# tactile_sensor.net
KiCad netlist of a schematic drawn in EAGLE
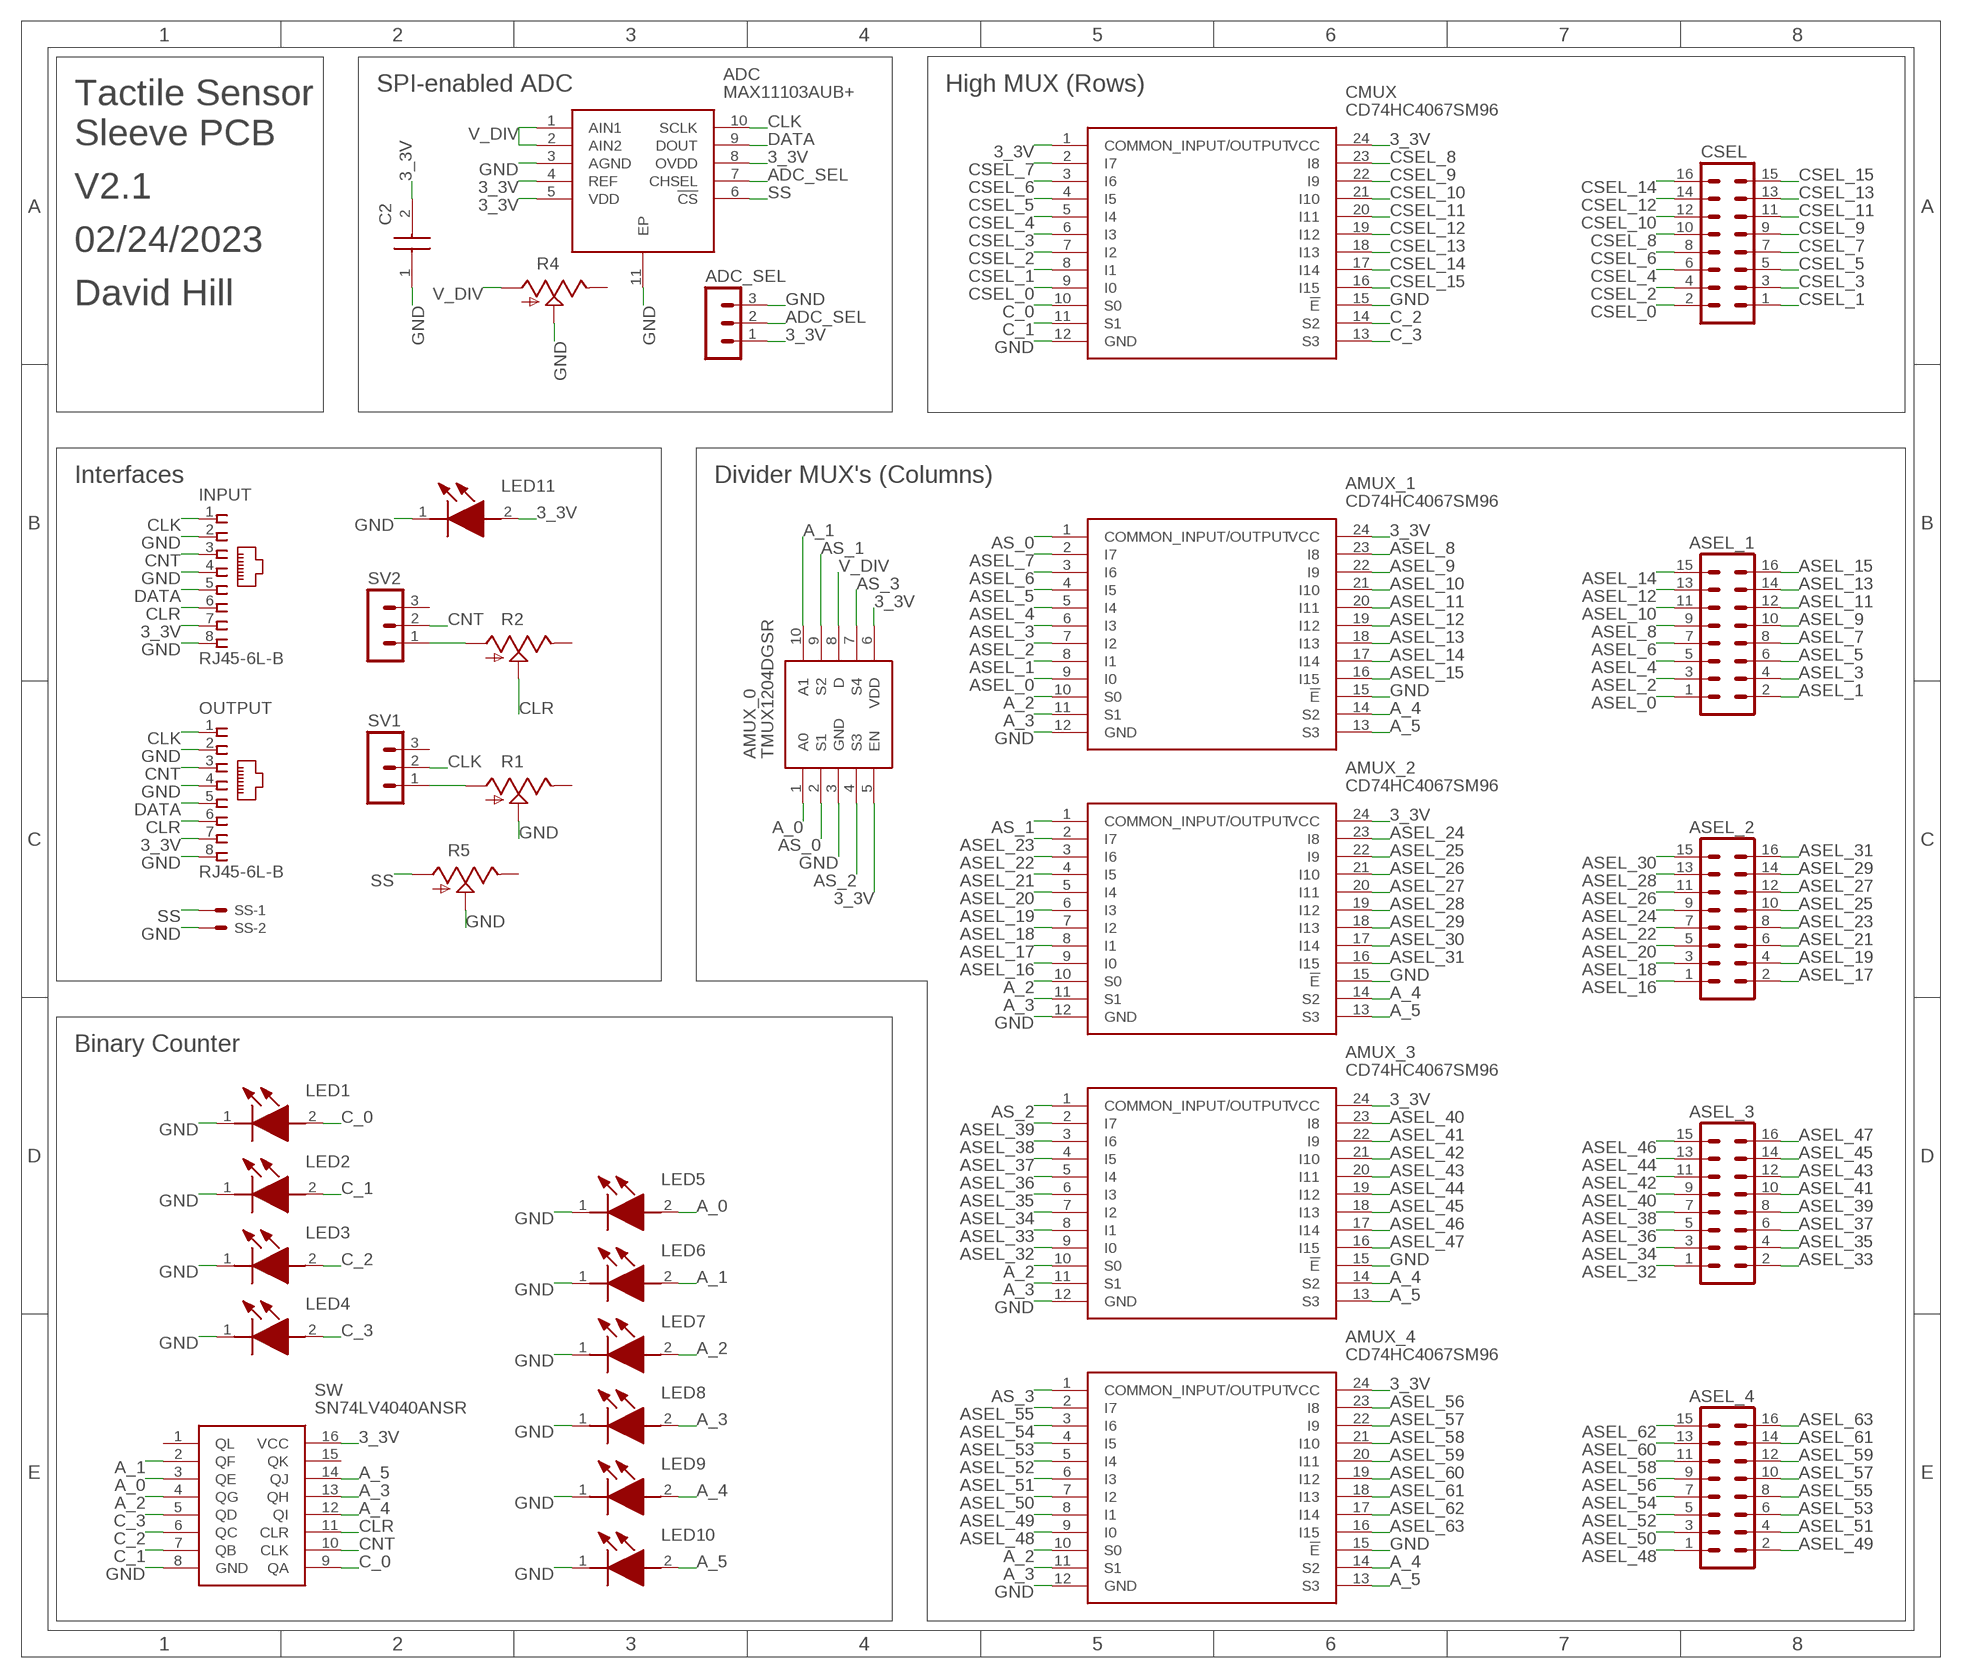
[diagram p0: schematic, sheet 1]

(export (version "E")
  (design (tool "Eeschema 10.0.6"))
  (components
    (comp (ref "ADC")
      (value "MAX11103AUB+")
      (footprint "eagle-import:SOP50P490X110-11N")
      (fields (field (name "MOUSER_PART_NUMBER") "700-MAX11103AUB+"))
      (libsource (lib "eagle-import") (part "MAX11103AUB+"))
    )
    (comp (ref "ADC_SEL")
      (value "MA03-1")
      (footprint "eagle-import:MA03-1")
      (libsource (lib "eagle-import") (part "MA03-1"))
    )
    (comp (ref "AMUX_0")
      (value "TMUX1204DGSR")
      (footprint "eagle-import:SOP50P490X110-10N")
      (fields (field (name "MOUSER_PART_NUMBER") "595-TMUX1204DGSR"))
      (libsource (lib "eagle-import") (part "TMUX1204DGSR"))
    )
    (comp (ref "AMUX_1")
      (value "CD74HC4067SM96")
      (footprint "eagle-import:SOP65P780X200-24N")
      (fields (field (name "MOUSER_PART_NUMBER") "595-CD74HC4067SM96"))
      (libsource (lib "eagle-import") (part "CD74HC4067SM96"))
    )
    (comp (ref "AMUX_2")
      (value "CD74HC4067SM96")
      (footprint "eagle-import:SOP65P780X200-24N")
      (fields (field (name "MOUSER_PART_NUMBER") "595-CD74HC4067SM96"))
      (libsource (lib "eagle-import") (part "CD74HC4067SM96"))
    )
    (comp (ref "AMUX_3")
      (value "CD74HC4067SM96")
      (footprint "eagle-import:SOP65P780X200-24N")
      (fields (field (name "MOUSER_PART_NUMBER") "595-CD74HC4067SM96"))
      (libsource (lib "eagle-import") (part "CD74HC4067SM96"))
    )
    (comp (ref "AMUX_4")
      (value "CD74HC4067SM96")
      (footprint "eagle-import:SOP65P780X200-24N")
      (fields (field (name "MOUSER_PART_NUMBER") "595-CD74HC4067SM96"))
      (libsource (lib "eagle-import") (part "CD74HC4067SM96"))
    )
    (comp (ref "ASEL_1")
      (value "MA08-2")
      (footprint "eagle-import:MA08-2")
      (libsource (lib "eagle-import") (part "MA08-2"))
    )
    (comp (ref "ASEL_2")
      (value "MA08-2")
      (footprint "eagle-import:MA08-2")
      (libsource (lib "eagle-import") (part "MA08-2"))
    )
    (comp (ref "ASEL_3")
      (value "MA08-2")
      (footprint "eagle-import:MA08-2")
      (libsource (lib "eagle-import") (part "MA08-2"))
    )
    (comp (ref "ASEL_4")
      (value "MA08-2")
      (footprint "eagle-import:MA08-2")
      (libsource (lib "eagle-import") (part "MA08-2"))
    )
    (comp (ref "C2")
      (value "C2012X7S1E106K125AE")
      (footprint "eagle-import:C2012_COMMERCIAL")
      (fields (field (name "MOUSER_PART_NUMBER") "810-C2012X7S1E106125"))
      (libsource (lib "eagle-import") (part "C2012X7S1E106K125AE"))
    )
    (comp (ref "CMUX")
      (value "CD74HC4067SM96")
      (footprint "eagle-import:SOP65P780X200-24N")
      (fields (field (name "MOUSER_PART_NUMBER") "595-CD74HC4067SM96"))
      (libsource (lib "eagle-import") (part "CD74HC4067SM96"))
    )
    (comp (ref "CSEL")
      (value "MA08-2")
      (footprint "eagle-import:MA08-2")
      (libsource (lib "eagle-import") (part "MA08-2"))
    )
    (comp (ref "INPUT")
      (value "RJ45-6L-B")
      (footprint "eagle-import:RJ45-NO-SHIELD")
      (libsource (lib "eagle-import") (part "RJ45-6L-B"))
    )
    (comp (ref "LED1")
      (value "APHCM2012QBC_D-F01")
      (footprint "eagle-import:APHCM2012QBCDF01")
      (fields
        (field (name "MANUFACTURER_PART_NUMBER") "APHCM2012QBC/D-F01")
        (field (name "MOUSER_PART_NUMBER") "604-APHCM2012QBC/D")
      )
      (libsource (lib "eagle-import") (part "APHCM2012QBC_D-F01"))
    )
    (comp (ref "LED2")
      (value "APHCM2012QBC_D-F01")
      (footprint "eagle-import:APHCM2012QBCDF01")
      (fields
        (field (name "MANUFACTURER_PART_NUMBER") "APHCM2012QBC/D-F01")
        (field (name "MOUSER_PART_NUMBER") "604-APHCM2012QBC/D")
      )
      (libsource (lib "eagle-import") (part "APHCM2012QBC_D-F01"))
    )
    (comp (ref "LED3")
      (value "APHCM2012QBC_D-F01")
      (footprint "eagle-import:APHCM2012QBCDF01")
      (fields
        (field (name "MANUFACTURER_PART_NUMBER") "APHCM2012QBC/D-F01")
        (field (name "MOUSER_PART_NUMBER") "604-APHCM2012QBC/D")
      )
      (libsource (lib "eagle-import") (part "APHCM2012QBC_D-F01"))
    )
    (comp (ref "LED4")
      (value "APHCM2012QBC_D-F01")
      (footprint "eagle-import:APHCM2012QBCDF01")
      (fields
        (field (name "MANUFACTURER_PART_NUMBER") "APHCM2012QBC/D-F01")
        (field (name "MOUSER_PART_NUMBER") "604-APHCM2012QBC/D")
      )
      (libsource (lib "eagle-import") (part "APHCM2012QBC_D-F01"))
    )
    (comp (ref "LED5")
      (value "APHCM2012QBC_D-F01")
      (footprint "eagle-import:APHCM2012QBCDF01")
      (fields
        (field (name "MANUFACTURER_PART_NUMBER") "APHCM2012QBC/D-F01")
        (field (name "MOUSER_PART_NUMBER") "604-APHCM2012QBC/D")
      )
      (libsource (lib "eagle-import") (part "APHCM2012QBC_D-F01"))
    )
    (comp (ref "LED6")
      (value "APHCM2012QBC_D-F01")
      (footprint "eagle-import:APHCM2012QBCDF01")
      (fields
        (field (name "MANUFACTURER_PART_NUMBER") "APHCM2012QBC/D-F01")
        (field (name "MOUSER_PART_NUMBER") "604-APHCM2012QBC/D")
      )
      (libsource (lib "eagle-import") (part "APHCM2012QBC_D-F01"))
    )
    (comp (ref "LED7")
      (value "APHCM2012QBC_D-F01")
      (footprint "eagle-import:APHCM2012QBCDF01")
      (fields
        (field (name "MANUFACTURER_PART_NUMBER") "APHCM2012QBC/D-F01")
        (field (name "MOUSER_PART_NUMBER") "604-APHCM2012QBC/D")
      )
      (libsource (lib "eagle-import") (part "APHCM2012QBC_D-F01"))
    )
    (comp (ref "LED8")
      (value "APHCM2012QBC_D-F01")
      (footprint "eagle-import:APHCM2012QBCDF01")
      (fields
        (field (name "MANUFACTURER_PART_NUMBER") "APHCM2012QBC/D-F01")
        (field (name "MOUSER_PART_NUMBER") "604-APHCM2012QBC/D")
      )
      (libsource (lib "eagle-import") (part "APHCM2012QBC_D-F01"))
    )
    (comp (ref "LED9")
      (value "APHCM2012QBC_D-F01")
      (footprint "eagle-import:APHCM2012QBCDF01")
      (fields
        (field (name "MANUFACTURER_PART_NUMBER") "APHCM2012QBC/D-F01")
        (field (name "MOUSER_PART_NUMBER") "604-APHCM2012QBC/D")
      )
      (libsource (lib "eagle-import") (part "APHCM2012QBC_D-F01"))
    )
    (comp (ref "LED10")
      (value "APHCM2012QBC_D-F01")
      (footprint "eagle-import:APHCM2012QBCDF01")
      (fields
        (field (name "MANUFACTURER_PART_NUMBER") "APHCM2012QBC/D-F01")
        (field (name "MOUSER_PART_NUMBER") "604-APHCM2012QBC/D")
      )
      (libsource (lib "eagle-import") (part "APHCM2012QBC_D-F01"))
    )
    (comp (ref "LED11")
      (value "APHCM2012QBC_D-F01")
      (footprint "eagle-import:APHCM2012QBCDF01")
      (fields
        (field (name "MANUFACTURER_PART_NUMBER") "APHCM2012QBC/D-F01")
        (field (name "MOUSER_PART_NUMBER") "604-APHCM2012QBC/D")
      )
      (libsource (lib "eagle-import") (part "APHCM2012QBC_D-F01"))
    )
    (comp (ref "OUTPUT")
      (value "RJ45-6L-B")
      (footprint "eagle-import:RJ45-NO-SHIELD")
      (libsource (lib "eagle-import") (part "RJ45-6L-B"))
    )
    (comp (ref "R1")
      (value "TRIM_US-B25P")
      (footprint "eagle-import:B25P")
      (libsource (lib "eagle-import") (part "TRIM_US-B25P"))
    )
    (comp (ref "R2")
      (value "TRIM_US-B25P")
      (footprint "eagle-import:B25P")
      (libsource (lib "eagle-import") (part "TRIM_US-B25P"))
    )
    (comp (ref "R4")
      (value "TRIM_US-B25P")
      (footprint "eagle-import:B25P")
      (libsource (lib "eagle-import") (part "TRIM_US-B25P"))
    )
    (comp (ref "R5")
      (value "TRIM_US-B25P")
      (footprint "eagle-import:B25P")
      (libsource (lib "eagle-import") (part "TRIM_US-B25P"))
    )
    (comp (ref "SS")
      (value "22-23-2021")
      (footprint "eagle-import:22-23-2021")
      (fields (field (name "MF") "MOLEX"))
      (libsource (lib "eagle-import") (part "22-23-2021"))
    )
    (comp (ref "SV1")
      (value "MA03-1")
      (footprint "eagle-import:MA03-1")
      (libsource (lib "eagle-import") (part "MA03-1"))
    )
    (comp (ref "SV2")
      (value "MA03-1")
      (footprint "eagle-import:MA03-1")
      (libsource (lib "eagle-import") (part "MA03-1"))
    )
    (comp (ref "SW")
      (value "SN74LV4040ANSR")
      (footprint "eagle-import:SOIC127P780X200-16N")
      (fields (field (name "MOUSER_PART_NUMBER") "595-SN74LV4040ANSR"))
      (libsource (lib "eagle-import") (part "SN74LV4040ANSR"))
    )
  )
  (nets
    (net (code "1") (name "/3_3V") (class "Default")
      (node (ref "ADC") (pin "4") (pinfunction "REF_4") (pintype "input"))
      (node (ref "ADC") (pin "5") (pinfunction "VDD_5") (pintype "power_in"))
      (node (ref "ADC") (pin "8") (pinfunction "OVDD_8") (pintype "power_in"))
      (node (ref "ADC_SEL") (pin "1") (pinfunction "1_1") (pintype "passive"))
      (node (ref "AMUX_0") (pin "5") (pinfunction "EN_5") (pintype "input"))
      (node (ref "AMUX_0") (pin "6") (pinfunction "VDD_6") (pintype "power_in"))
      (node (ref "AMUX_1") (pin "24") (pinfunction "VCC_24") (pintype "bidirectional"))
      (node (ref "AMUX_2") (pin "24") (pinfunction "VCC_24") (pintype "bidirectional"))
      (node (ref "AMUX_3") (pin "24") (pinfunction "VCC_24") (pintype "bidirectional"))
      (node (ref "AMUX_4") (pin "24") (pinfunction "VCC_24") (pintype "bidirectional"))
      (node (ref "C2") (pin "2") (pinfunction "2_2") (pintype "bidirectional"))
      (node (ref "CMUX") (pin "1") (pinfunction "COMMON_INPUT/OUTPUT_1") (pintype "bidirectional"))
      (node (ref "CMUX") (pin "24") (pinfunction "VCC_24") (pintype "bidirectional"))
      (node (ref "INPUT") (pin "7") (pinfunction "7_7") (pintype "passive"))
      (node (ref "LED11") (pin "2") (pinfunction "A_2") (pintype "bidirectional"))
      (node (ref "OUTPUT") (pin "7") (pinfunction "7_7") (pintype "passive"))
      (node (ref "SW") (pin "16") (pinfunction "VCC_16") (pintype "bidirectional"))
    )
    (net (code "2") (name "/ADC_SEL") (class "Default")
      (node (ref "ADC") (pin "7") (pinfunction "CHSEL_7") (pintype "bidirectional"))
      (node (ref "ADC_SEL") (pin "2") (pinfunction "2_2") (pintype "passive"))
    )
    (net (code "3") (name "/ASEL_0") (class "Default")
      (node (ref "AMUX_1") (pin "9") (pinfunction "I0_9") (pintype "bidirectional"))
      (node (ref "ASEL_1") (pin "1") (pinfunction "1_1") (pintype "passive"))
    )
    (net (code "4") (name "/ASEL_1") (class "Default")
      (node (ref "AMUX_1") (pin "8") (pinfunction "I1_8") (pintype "bidirectional"))
      (node (ref "ASEL_1") (pin "2") (pinfunction "2_2") (pintype "passive"))
    )
    (net (code "5") (name "/ASEL_2") (class "Default")
      (node (ref "AMUX_1") (pin "7") (pinfunction "I2_7") (pintype "bidirectional"))
      (node (ref "ASEL_1") (pin "3") (pinfunction "3_3") (pintype "passive"))
    )
    (net (code "6") (name "/ASEL_3") (class "Default")
      (node (ref "AMUX_1") (pin "6") (pinfunction "I3_6") (pintype "bidirectional"))
      (node (ref "ASEL_1") (pin "4") (pinfunction "4_4") (pintype "passive"))
    )
    (net (code "7") (name "/ASEL_4") (class "Default")
      (node (ref "AMUX_1") (pin "5") (pinfunction "I4_5") (pintype "bidirectional"))
      (node (ref "ASEL_1") (pin "5") (pinfunction "5_5") (pintype "passive"))
    )
    (net (code "8") (name "/ASEL_5") (class "Default")
      (node (ref "AMUX_1") (pin "4") (pinfunction "I5_4") (pintype "bidirectional"))
      (node (ref "ASEL_1") (pin "6") (pinfunction "6_6") (pintype "passive"))
    )
    (net (code "9") (name "/ASEL_6") (class "Default")
      (node (ref "AMUX_1") (pin "3") (pinfunction "I6_3") (pintype "bidirectional"))
      (node (ref "ASEL_1") (pin "7") (pinfunction "7_7") (pintype "passive"))
    )
    (net (code "10") (name "/ASEL_7") (class "Default")
      (node (ref "AMUX_1") (pin "2") (pinfunction "I7_2") (pintype "bidirectional"))
      (node (ref "ASEL_1") (pin "8") (pinfunction "8_8") (pintype "passive"))
    )
    (net (code "11") (name "/ASEL_8") (class "Default")
      (node (ref "AMUX_1") (pin "23") (pinfunction "I8_23") (pintype "bidirectional"))
      (node (ref "ASEL_1") (pin "9") (pinfunction "9_9") (pintype "passive"))
    )
    (net (code "12") (name "/ASEL_9") (class "Default")
      (node (ref "AMUX_1") (pin "22") (pinfunction "I9_22") (pintype "bidirectional"))
      (node (ref "ASEL_1") (pin "10") (pinfunction "10_10") (pintype "passive"))
    )
    (net (code "13") (name "/ASEL_10") (class "Default")
      (node (ref "AMUX_1") (pin "21") (pinfunction "I10_21") (pintype "bidirectional"))
      (node (ref "ASEL_1") (pin "11") (pinfunction "11_11") (pintype "passive"))
    )
    (net (code "14") (name "/ASEL_11") (class "Default")
      (node (ref "AMUX_1") (pin "20") (pinfunction "I11_20") (pintype "bidirectional"))
      (node (ref "ASEL_1") (pin "12") (pinfunction "12_12") (pintype "passive"))
    )
    (net (code "15") (name "/ASEL_12") (class "Default")
      (node (ref "AMUX_1") (pin "19") (pinfunction "I12_19") (pintype "bidirectional"))
      (node (ref "ASEL_1") (pin "13") (pinfunction "13_13") (pintype "passive"))
    )
    (net (code "16") (name "/ASEL_13") (class "Default")
      (node (ref "AMUX_1") (pin "18") (pinfunction "I13_18") (pintype "bidirectional"))
      (node (ref "ASEL_1") (pin "14") (pinfunction "14_14") (pintype "passive"))
    )
    (net (code "17") (name "/ASEL_14") (class "Default")
      (node (ref "AMUX_1") (pin "17") (pinfunction "I14_17") (pintype "bidirectional"))
      (node (ref "ASEL_1") (pin "15") (pinfunction "15_15") (pintype "passive"))
    )
    (net (code "18") (name "/ASEL_15") (class "Default")
      (node (ref "AMUX_1") (pin "16") (pinfunction "I15_16") (pintype "bidirectional"))
      (node (ref "ASEL_1") (pin "16") (pinfunction "16_16") (pintype "passive"))
    )
    (net (code "19") (name "/ASEL_16") (class "Default")
      (node (ref "AMUX_2") (pin "9") (pinfunction "I0_9") (pintype "bidirectional"))
      (node (ref "ASEL_2") (pin "1") (pinfunction "1_1") (pintype "passive"))
    )
    (net (code "20") (name "/ASEL_17") (class "Default")
      (node (ref "AMUX_2") (pin "8") (pinfunction "I1_8") (pintype "bidirectional"))
      (node (ref "ASEL_2") (pin "2") (pinfunction "2_2") (pintype "passive"))
    )
    (net (code "21") (name "/ASEL_18") (class "Default")
      (node (ref "AMUX_2") (pin "7") (pinfunction "I2_7") (pintype "bidirectional"))
      (node (ref "ASEL_2") (pin "3") (pinfunction "3_3") (pintype "passive"))
    )
    (net (code "22") (name "/ASEL_19") (class "Default")
      (node (ref "AMUX_2") (pin "6") (pinfunction "I3_6") (pintype "bidirectional"))
      (node (ref "ASEL_2") (pin "4") (pinfunction "4_4") (pintype "passive"))
    )
    (net (code "23") (name "/ASEL_20") (class "Default")
      (node (ref "AMUX_2") (pin "5") (pinfunction "I4_5") (pintype "bidirectional"))
      (node (ref "ASEL_2") (pin "5") (pinfunction "5_5") (pintype "passive"))
    )
    (net (code "24") (name "/ASEL_21") (class "Default")
      (node (ref "AMUX_2") (pin "4") (pinfunction "I5_4") (pintype "bidirectional"))
      (node (ref "ASEL_2") (pin "6") (pinfunction "6_6") (pintype "passive"))
    )
    (net (code "25") (name "/ASEL_22") (class "Default")
      (node (ref "AMUX_2") (pin "3") (pinfunction "I6_3") (pintype "bidirectional"))
      (node (ref "ASEL_2") (pin "7") (pinfunction "7_7") (pintype "passive"))
    )
    (net (code "26") (name "/ASEL_23") (class "Default")
      (node (ref "AMUX_2") (pin "2") (pinfunction "I7_2") (pintype "bidirectional"))
      (node (ref "ASEL_2") (pin "8") (pinfunction "8_8") (pintype "passive"))
    )
    (net (code "27") (name "/ASEL_24") (class "Default")
      (node (ref "AMUX_2") (pin "23") (pinfunction "I8_23") (pintype "bidirectional"))
      (node (ref "ASEL_2") (pin "9") (pinfunction "9_9") (pintype "passive"))
    )
    (net (code "28") (name "/ASEL_25") (class "Default")
      (node (ref "AMUX_2") (pin "22") (pinfunction "I9_22") (pintype "bidirectional"))
      (node (ref "ASEL_2") (pin "10") (pinfunction "10_10") (pintype "passive"))
    )
    (net (code "29") (name "/ASEL_26") (class "Default")
      (node (ref "AMUX_2") (pin "21") (pinfunction "I10_21") (pintype "bidirectional"))
      (node (ref "ASEL_2") (pin "11") (pinfunction "11_11") (pintype "passive"))
    )
    (net (code "30") (name "/ASEL_27") (class "Default")
      (node (ref "AMUX_2") (pin "20") (pinfunction "I11_20") (pintype "bidirectional"))
      (node (ref "ASEL_2") (pin "12") (pinfunction "12_12") (pintype "passive"))
    )
    (net (code "31") (name "/ASEL_28") (class "Default")
      (node (ref "AMUX_2") (pin "19") (pinfunction "I12_19") (pintype "bidirectional"))
      (node (ref "ASEL_2") (pin "13") (pinfunction "13_13") (pintype "passive"))
    )
    (net (code "32") (name "/ASEL_29") (class "Default")
      (node (ref "AMUX_2") (pin "18") (pinfunction "I13_18") (pintype "bidirectional"))
      (node (ref "ASEL_2") (pin "14") (pinfunction "14_14") (pintype "passive"))
    )
    (net (code "33") (name "/ASEL_30") (class "Default")
      (node (ref "AMUX_2") (pin "17") (pinfunction "I14_17") (pintype "bidirectional"))
      (node (ref "ASEL_2") (pin "15") (pinfunction "15_15") (pintype "passive"))
    )
    (net (code "34") (name "/ASEL_31") (class "Default")
      (node (ref "AMUX_2") (pin "16") (pinfunction "I15_16") (pintype "bidirectional"))
      (node (ref "ASEL_2") (pin "16") (pinfunction "16_16") (pintype "passive"))
    )
    (net (code "35") (name "/ASEL_32") (class "Default")
      (node (ref "AMUX_3") (pin "9") (pinfunction "I0_9") (pintype "bidirectional"))
      (node (ref "ASEL_3") (pin "1") (pinfunction "1_1") (pintype "passive"))
    )
    (net (code "36") (name "/ASEL_33") (class "Default")
      (node (ref "AMUX_3") (pin "8") (pinfunction "I1_8") (pintype "bidirectional"))
      (node (ref "ASEL_3") (pin "2") (pinfunction "2_2") (pintype "passive"))
    )
    (net (code "37") (name "/ASEL_34") (class "Default")
      (node (ref "AMUX_3") (pin "7") (pinfunction "I2_7") (pintype "bidirectional"))
      (node (ref "ASEL_3") (pin "3") (pinfunction "3_3") (pintype "passive"))
    )
    (net (code "38") (name "/ASEL_35") (class "Default")
      (node (ref "AMUX_3") (pin "6") (pinfunction "I3_6") (pintype "bidirectional"))
      (node (ref "ASEL_3") (pin "4") (pinfunction "4_4") (pintype "passive"))
    )
    (net (code "39") (name "/ASEL_36") (class "Default")
      (node (ref "AMUX_3") (pin "5") (pinfunction "I4_5") (pintype "bidirectional"))
      (node (ref "ASEL_3") (pin "5") (pinfunction "5_5") (pintype "passive"))
    )
    (net (code "40") (name "/ASEL_37") (class "Default")
      (node (ref "AMUX_3") (pin "4") (pinfunction "I5_4") (pintype "bidirectional"))
      (node (ref "ASEL_3") (pin "6") (pinfunction "6_6") (pintype "passive"))
    )
    (net (code "41") (name "/ASEL_38") (class "Default")
      (node (ref "AMUX_3") (pin "3") (pinfunction "I6_3") (pintype "bidirectional"))
      (node (ref "ASEL_3") (pin "7") (pinfunction "7_7") (pintype "passive"))
    )
    (net (code "42") (name "/ASEL_39") (class "Default")
      (node (ref "AMUX_3") (pin "2") (pinfunction "I7_2") (pintype "bidirectional"))
      (node (ref "ASEL_3") (pin "8") (pinfunction "8_8") (pintype "passive"))
    )
    (net (code "43") (name "/ASEL_40") (class "Default")
      (node (ref "AMUX_3") (pin "23") (pinfunction "I8_23") (pintype "bidirectional"))
      (node (ref "ASEL_3") (pin "9") (pinfunction "9_9") (pintype "passive"))
    )
    (net (code "44") (name "/ASEL_41") (class "Default")
      (node (ref "AMUX_3") (pin "22") (pinfunction "I9_22") (pintype "bidirectional"))
      (node (ref "ASEL_3") (pin "10") (pinfunction "10_10") (pintype "passive"))
    )
    (net (code "45") (name "/ASEL_42") (class "Default")
      (node (ref "AMUX_3") (pin "21") (pinfunction "I10_21") (pintype "bidirectional"))
      (node (ref "ASEL_3") (pin "11") (pinfunction "11_11") (pintype "passive"))
    )
    (net (code "46") (name "/ASEL_43") (class "Default")
      (node (ref "AMUX_3") (pin "20") (pinfunction "I11_20") (pintype "bidirectional"))
      (node (ref "ASEL_3") (pin "12") (pinfunction "12_12") (pintype "passive"))
    )
    (net (code "47") (name "/ASEL_44") (class "Default")
      (node (ref "AMUX_3") (pin "19") (pinfunction "I12_19") (pintype "bidirectional"))
      (node (ref "ASEL_3") (pin "13") (pinfunction "13_13") (pintype "passive"))
    )
    (net (code "48") (name "/ASEL_45") (class "Default")
      (node (ref "AMUX_3") (pin "18") (pinfunction "I13_18") (pintype "bidirectional"))
      (node (ref "ASEL_3") (pin "14") (pinfunction "14_14") (pintype "passive"))
    )
    (net (code "49") (name "/ASEL_46") (class "Default")
      (node (ref "AMUX_3") (pin "17") (pinfunction "I14_17") (pintype "bidirectional"))
      (node (ref "ASEL_3") (pin "15") (pinfunction "15_15") (pintype "passive"))
    )
    (net (code "50") (name "/ASEL_47") (class "Default")
      (node (ref "AMUX_3") (pin "16") (pinfunction "I15_16") (pintype "bidirectional"))
      (node (ref "ASEL_3") (pin "16") (pinfunction "16_16") (pintype "passive"))
    )
    (net (code "51") (name "/ASEL_48") (class "Default")
      (node (ref "AMUX_4") (pin "9") (pinfunction "I0_9") (pintype "bidirectional"))
      (node (ref "ASEL_4") (pin "1") (pinfunction "1_1") (pintype "passive"))
    )
    (net (code "52") (name "/ASEL_49") (class "Default")
      (node (ref "AMUX_4") (pin "8") (pinfunction "I1_8") (pintype "bidirectional"))
      (node (ref "ASEL_4") (pin "2") (pinfunction "2_2") (pintype "passive"))
    )
    (net (code "53") (name "/ASEL_50") (class "Default")
      (node (ref "AMUX_4") (pin "7") (pinfunction "I2_7") (pintype "bidirectional"))
      (node (ref "ASEL_4") (pin "3") (pinfunction "3_3") (pintype "passive"))
    )
    (net (code "54") (name "/ASEL_51") (class "Default")
      (node (ref "AMUX_4") (pin "6") (pinfunction "I3_6") (pintype "bidirectional"))
      (node (ref "ASEL_4") (pin "4") (pinfunction "4_4") (pintype "passive"))
    )
    (net (code "55") (name "/ASEL_52") (class "Default")
      (node (ref "AMUX_4") (pin "5") (pinfunction "I4_5") (pintype "bidirectional"))
      (node (ref "ASEL_4") (pin "5") (pinfunction "5_5") (pintype "passive"))
    )
    (net (code "56") (name "/ASEL_53") (class "Default")
      (node (ref "AMUX_4") (pin "4") (pinfunction "I5_4") (pintype "bidirectional"))
      (node (ref "ASEL_4") (pin "6") (pinfunction "6_6") (pintype "passive"))
    )
    (net (code "57") (name "/ASEL_54") (class "Default")
      (node (ref "AMUX_4") (pin "3") (pinfunction "I6_3") (pintype "bidirectional"))
      (node (ref "ASEL_4") (pin "7") (pinfunction "7_7") (pintype "passive"))
    )
    (net (code "58") (name "/ASEL_55") (class "Default")
      (node (ref "AMUX_4") (pin "2") (pinfunction "I7_2") (pintype "bidirectional"))
      (node (ref "ASEL_4") (pin "8") (pinfunction "8_8") (pintype "passive"))
    )
    (net (code "59") (name "/ASEL_56") (class "Default")
      (node (ref "AMUX_4") (pin "23") (pinfunction "I8_23") (pintype "bidirectional"))
      (node (ref "ASEL_4") (pin "9") (pinfunction "9_9") (pintype "passive"))
    )
    (net (code "60") (name "/ASEL_57") (class "Default")
      (node (ref "AMUX_4") (pin "22") (pinfunction "I9_22") (pintype "bidirectional"))
      (node (ref "ASEL_4") (pin "10") (pinfunction "10_10") (pintype "passive"))
    )
    (net (code "61") (name "/ASEL_58") (class "Default")
      (node (ref "AMUX_4") (pin "21") (pinfunction "I10_21") (pintype "bidirectional"))
      (node (ref "ASEL_4") (pin "11") (pinfunction "11_11") (pintype "passive"))
    )
    (net (code "62") (name "/ASEL_59") (class "Default")
      (node (ref "AMUX_4") (pin "20") (pinfunction "I11_20") (pintype "bidirectional"))
      (node (ref "ASEL_4") (pin "12") (pinfunction "12_12") (pintype "passive"))
    )
    (net (code "63") (name "/ASEL_60") (class "Default")
      (node (ref "AMUX_4") (pin "19") (pinfunction "I12_19") (pintype "bidirectional"))
      (node (ref "ASEL_4") (pin "13") (pinfunction "13_13") (pintype "passive"))
    )
    (net (code "64") (name "/ASEL_61") (class "Default")
      (node (ref "AMUX_4") (pin "18") (pinfunction "I13_18") (pintype "bidirectional"))
      (node (ref "ASEL_4") (pin "14") (pinfunction "14_14") (pintype "passive"))
    )
    (net (code "65") (name "/ASEL_62") (class "Default")
      (node (ref "AMUX_4") (pin "17") (pinfunction "I14_17") (pintype "bidirectional"))
      (node (ref "ASEL_4") (pin "15") (pinfunction "15_15") (pintype "passive"))
    )
    (net (code "66") (name "/ASEL_63") (class "Default")
      (node (ref "AMUX_4") (pin "16") (pinfunction "I15_16") (pintype "bidirectional"))
      (node (ref "ASEL_4") (pin "16") (pinfunction "16_16") (pintype "passive"))
    )
    (net (code "67") (name "/AS_0") (class "Default")
      (node (ref "AMUX_0") (pin "2") (pinfunction "S1_2") (pintype "bidirectional"))
      (node (ref "AMUX_1") (pin "1") (pinfunction "COMMON_INPUT/OUTPUT_1") (pintype "bidirectional"))
    )
    (net (code "68") (name "/AS_1") (class "Default")
      (node (ref "AMUX_0") (pin "9") (pinfunction "S2_9") (pintype "bidirectional"))
      (node (ref "AMUX_2") (pin "1") (pinfunction "COMMON_INPUT/OUTPUT_1") (pintype "bidirectional"))
    )
    (net (code "69") (name "/AS_2") (class "Default")
      (node (ref "AMUX_0") (pin "4") (pinfunction "S3_4") (pintype "bidirectional"))
      (node (ref "AMUX_3") (pin "1") (pinfunction "COMMON_INPUT/OUTPUT_1") (pintype "bidirectional"))
    )
    (net (code "70") (name "/AS_3") (class "Default")
      (node (ref "AMUX_0") (pin "7") (pinfunction "S4_7") (pintype "bidirectional"))
      (node (ref "AMUX_4") (pin "1") (pinfunction "COMMON_INPUT/OUTPUT_1") (pintype "bidirectional"))
    )
    (net (code "71") (name "/A_0") (class "Default")
      (node (ref "AMUX_0") (pin "1") (pinfunction "A0_1") (pintype "input"))
      (node (ref "LED5") (pin "2") (pinfunction "A_2") (pintype "bidirectional"))
      (node (ref "SW") (pin "3") (pinfunction "QE_3") (pintype "bidirectional"))
    )
    (net (code "72") (name "/A_1") (class "Default")
      (node (ref "AMUX_0") (pin "10") (pinfunction "A1_10") (pintype "input"))
      (node (ref "LED6") (pin "2") (pinfunction "A_2") (pintype "bidirectional"))
      (node (ref "SW") (pin "2") (pinfunction "QF_2") (pintype "bidirectional"))
    )
    (net (code "73") (name "/A_2") (class "Default")
      (node (ref "AMUX_1") (pin "10") (pinfunction "S0_10") (pintype "bidirectional"))
      (node (ref "AMUX_2") (pin "10") (pinfunction "S0_10") (pintype "bidirectional"))
      (node (ref "AMUX_3") (pin "10") (pinfunction "S0_10") (pintype "bidirectional"))
      (node (ref "AMUX_4") (pin "10") (pinfunction "S0_10") (pintype "bidirectional"))
      (node (ref "LED7") (pin "2") (pinfunction "A_2") (pintype "bidirectional"))
      (node (ref "SW") (pin "4") (pinfunction "QG_4") (pintype "bidirectional"))
    )
    (net (code "74") (name "/A_3") (class "Default")
      (node (ref "AMUX_1") (pin "11") (pinfunction "S1_11") (pintype "bidirectional"))
      (node (ref "AMUX_2") (pin "11") (pinfunction "S1_11") (pintype "bidirectional"))
      (node (ref "AMUX_3") (pin "11") (pinfunction "S1_11") (pintype "bidirectional"))
      (node (ref "AMUX_4") (pin "11") (pinfunction "S1_11") (pintype "bidirectional"))
      (node (ref "LED8") (pin "2") (pinfunction "A_2") (pintype "bidirectional"))
      (node (ref "SW") (pin "13") (pinfunction "QH_13") (pintype "bidirectional"))
    )
    (net (code "75") (name "/A_4") (class "Default")
      (node (ref "AMUX_1") (pin "14") (pinfunction "S2_14") (pintype "bidirectional"))
      (node (ref "AMUX_2") (pin "14") (pinfunction "S2_14") (pintype "bidirectional"))
      (node (ref "AMUX_3") (pin "14") (pinfunction "S2_14") (pintype "bidirectional"))
      (node (ref "AMUX_4") (pin "14") (pinfunction "S2_14") (pintype "bidirectional"))
      (node (ref "LED9") (pin "2") (pinfunction "A_2") (pintype "bidirectional"))
      (node (ref "SW") (pin "12") (pinfunction "QI_12") (pintype "bidirectional"))
    )
    (net (code "76") (name "/A_5") (class "Default")
      (node (ref "AMUX_1") (pin "13") (pinfunction "S3_13") (pintype "bidirectional"))
      (node (ref "AMUX_2") (pin "13") (pinfunction "S3_13") (pintype "bidirectional"))
      (node (ref "AMUX_3") (pin "13") (pinfunction "S3_13") (pintype "bidirectional"))
      (node (ref "AMUX_4") (pin "13") (pinfunction "S3_13") (pintype "bidirectional"))
      (node (ref "LED10") (pin "2") (pinfunction "A_2") (pintype "bidirectional"))
      (node (ref "SW") (pin "14") (pinfunction "QJ_14") (pintype "bidirectional"))
    )
    (net (code "77") (name "/CLK") (class "Default")
      (node (ref "ADC") (pin "10") (pinfunction "SCLK_10") (pintype "input"))
      (node (ref "INPUT") (pin "1") (pinfunction "1_1") (pintype "passive"))
      (node (ref "OUTPUT") (pin "1") (pinfunction "1_1") (pintype "passive"))
      (node (ref "SV1") (pin "2") (pinfunction "2_2") (pintype "passive"))
    )
    (net (code "78") (name "/CLR") (class "Default")
      (node (ref "INPUT") (pin "6") (pinfunction "6_6") (pintype "passive"))
      (node (ref "OUTPUT") (pin "6") (pinfunction "6_6") (pintype "passive"))
      (node (ref "R2") (pin "S") (pinfunction "S_S") (pintype "passive"))
      (node (ref "SW") (pin "11") (pinfunction "CLR_11") (pintype "bidirectional"))
    )
    (net (code "79") (name "/CNT") (class "Default")
      (node (ref "INPUT") (pin "3") (pinfunction "3_3") (pintype "passive"))
      (node (ref "OUTPUT") (pin "3") (pinfunction "3_3") (pintype "passive"))
      (node (ref "SV2") (pin "2") (pinfunction "2_2") (pintype "passive"))
      (node (ref "SW") (pin "10") (pinfunction "CLK_10") (pintype "bidirectional"))
    )
    (net (code "80") (name "/CSEL_0") (class "Default")
      (node (ref "CMUX") (pin "9") (pinfunction "I0_9") (pintype "bidirectional"))
      (node (ref "CSEL") (pin "2") (pinfunction "2_2") (pintype "passive"))
    )
    (net (code "81") (name "/CSEL_1") (class "Default")
      (node (ref "CMUX") (pin "8") (pinfunction "I1_8") (pintype "bidirectional"))
      (node (ref "CSEL") (pin "1") (pinfunction "1_1") (pintype "passive"))
    )
    (net (code "82") (name "/CSEL_2") (class "Default")
      (node (ref "CMUX") (pin "7") (pinfunction "I2_7") (pintype "bidirectional"))
      (node (ref "CSEL") (pin "4") (pinfunction "4_4") (pintype "passive"))
    )
    (net (code "83") (name "/CSEL_3") (class "Default")
      (node (ref "CMUX") (pin "6") (pinfunction "I3_6") (pintype "bidirectional"))
      (node (ref "CSEL") (pin "3") (pinfunction "3_3") (pintype "passive"))
    )
    (net (code "84") (name "/CSEL_4") (class "Default")
      (node (ref "CMUX") (pin "5") (pinfunction "I4_5") (pintype "bidirectional"))
      (node (ref "CSEL") (pin "6") (pinfunction "6_6") (pintype "passive"))
    )
    (net (code "85") (name "/CSEL_5") (class "Default")
      (node (ref "CMUX") (pin "4") (pinfunction "I5_4") (pintype "bidirectional"))
      (node (ref "CSEL") (pin "5") (pinfunction "5_5") (pintype "passive"))
    )
    (net (code "86") (name "/CSEL_6") (class "Default")
      (node (ref "CMUX") (pin "3") (pinfunction "I6_3") (pintype "bidirectional"))
      (node (ref "CSEL") (pin "8") (pinfunction "8_8") (pintype "passive"))
    )
    (net (code "87") (name "/CSEL_7") (class "Default")
      (node (ref "CMUX") (pin "2") (pinfunction "I7_2") (pintype "bidirectional"))
      (node (ref "CSEL") (pin "7") (pinfunction "7_7") (pintype "passive"))
    )
    (net (code "88") (name "/CSEL_8") (class "Default")
      (node (ref "CMUX") (pin "23") (pinfunction "I8_23") (pintype "bidirectional"))
      (node (ref "CSEL") (pin "10") (pinfunction "10_10") (pintype "passive"))
    )
    (net (code "89") (name "/CSEL_9") (class "Default")
      (node (ref "CMUX") (pin "22") (pinfunction "I9_22") (pintype "bidirectional"))
      (node (ref "CSEL") (pin "9") (pinfunction "9_9") (pintype "passive"))
    )
    (net (code "90") (name "/CSEL_10") (class "Default")
      (node (ref "CMUX") (pin "21") (pinfunction "I10_21") (pintype "bidirectional"))
      (node (ref "CSEL") (pin "12") (pinfunction "12_12") (pintype "passive"))
    )
    (net (code "91") (name "/CSEL_11") (class "Default")
      (node (ref "CMUX") (pin "20") (pinfunction "I11_20") (pintype "bidirectional"))
      (node (ref "CSEL") (pin "11") (pinfunction "11_11") (pintype "passive"))
    )
    (net (code "92") (name "/CSEL_12") (class "Default")
      (node (ref "CMUX") (pin "19") (pinfunction "I12_19") (pintype "bidirectional"))
      (node (ref "CSEL") (pin "14") (pinfunction "14_14") (pintype "passive"))
    )
    (net (code "93") (name "/CSEL_13") (class "Default")
      (node (ref "CMUX") (pin "18") (pinfunction "I13_18") (pintype "bidirectional"))
      (node (ref "CSEL") (pin "13") (pinfunction "13_13") (pintype "passive"))
    )
    (net (code "94") (name "/CSEL_14") (class "Default")
      (node (ref "CMUX") (pin "17") (pinfunction "I14_17") (pintype "bidirectional"))
      (node (ref "CSEL") (pin "16") (pinfunction "16_16") (pintype "passive"))
    )
    (net (code "95") (name "/CSEL_15") (class "Default")
      (node (ref "CMUX") (pin "16") (pinfunction "I15_16") (pintype "bidirectional"))
      (node (ref "CSEL") (pin "15") (pinfunction "15_15") (pintype "passive"))
    )
    (net (code "96") (name "/C_0") (class "Default")
      (node (ref "CMUX") (pin "10") (pinfunction "S0_10") (pintype "bidirectional"))
      (node (ref "LED1") (pin "2") (pinfunction "A_2") (pintype "bidirectional"))
      (node (ref "SW") (pin "9") (pinfunction "QA_9") (pintype "bidirectional"))
    )
    (net (code "97") (name "/C_1") (class "Default")
      (node (ref "CMUX") (pin "11") (pinfunction "S1_11") (pintype "bidirectional"))
      (node (ref "LED2") (pin "2") (pinfunction "A_2") (pintype "bidirectional"))
      (node (ref "SW") (pin "7") (pinfunction "QB_7") (pintype "bidirectional"))
    )
    (net (code "98") (name "/C_2") (class "Default")
      (node (ref "CMUX") (pin "14") (pinfunction "S2_14") (pintype "bidirectional"))
      (node (ref "LED3") (pin "2") (pinfunction "A_2") (pintype "bidirectional"))
      (node (ref "SW") (pin "6") (pinfunction "QC_6") (pintype "bidirectional"))
    )
    (net (code "99") (name "/C_3") (class "Default")
      (node (ref "CMUX") (pin "13") (pinfunction "S3_13") (pintype "bidirectional"))
      (node (ref "LED4") (pin "2") (pinfunction "A_2") (pintype "bidirectional"))
      (node (ref "SW") (pin "5") (pinfunction "QD_5") (pintype "bidirectional"))
    )
    (net (code "100") (name "/DATA") (class "Default")
      (node (ref "ADC") (pin "9") (pinfunction "DOUT_9") (pintype "output"))
      (node (ref "INPUT") (pin "5") (pinfunction "5_5") (pintype "passive"))
      (node (ref "OUTPUT") (pin "5") (pinfunction "5_5") (pintype "passive"))
    )
    (net (code "101") (name "/GND") (class "Default")
      (node (ref "ADC") (pin "11") (pinfunction "EP_11") (pintype "power_in"))
      (node (ref "ADC") (pin "3") (pinfunction "AGND_3") (pintype "power_in"))
      (node (ref "ADC_SEL") (pin "3") (pinfunction "3_3") (pintype "passive"))
      (node (ref "AMUX_0") (pin "3") (pinfunction "GND_3") (pintype "power_in"))
      (node (ref "AMUX_1") (pin "12") (pinfunction "GND_12") (pintype "bidirectional"))
      (node (ref "AMUX_1") (pin "15") (pinfunction "~{E}_15") (pintype "bidirectional"))
      (node (ref "AMUX_2") (pin "12") (pinfunction "GND_12") (pintype "bidirectional"))
      (node (ref "AMUX_2") (pin "15") (pinfunction "~{E}_15") (pintype "bidirectional"))
      (node (ref "AMUX_3") (pin "12") (pinfunction "GND_12") (pintype "bidirectional"))
      (node (ref "AMUX_3") (pin "15") (pinfunction "~{E}_15") (pintype "bidirectional"))
      (node (ref "AMUX_4") (pin "12") (pinfunction "GND_12") (pintype "bidirectional"))
      (node (ref "AMUX_4") (pin "15") (pinfunction "~{E}_15") (pintype "bidirectional"))
      (node (ref "C2") (pin "1") (pinfunction "1_1") (pintype "bidirectional"))
      (node (ref "CMUX") (pin "12") (pinfunction "GND_12") (pintype "bidirectional"))
      (node (ref "CMUX") (pin "15") (pinfunction "~{E}_15") (pintype "bidirectional"))
      (node (ref "INPUT") (pin "2") (pinfunction "2_2") (pintype "passive"))
      (node (ref "INPUT") (pin "4") (pinfunction "4_4") (pintype "passive"))
      (node (ref "INPUT") (pin "8") (pinfunction "8_8") (pintype "passive"))
      (node (ref "LED1") (pin "1") (pinfunction "K_1") (pintype "bidirectional"))
      (node (ref "LED10") (pin "1") (pinfunction "K_1") (pintype "bidirectional"))
      (node (ref "LED11") (pin "1") (pinfunction "K_1") (pintype "bidirectional"))
      (node (ref "LED2") (pin "1") (pinfunction "K_1") (pintype "bidirectional"))
      (node (ref "LED3") (pin "1") (pinfunction "K_1") (pintype "bidirectional"))
      (node (ref "LED4") (pin "1") (pinfunction "K_1") (pintype "bidirectional"))
      (node (ref "LED5") (pin "1") (pinfunction "K_1") (pintype "bidirectional"))
      (node (ref "LED6") (pin "1") (pinfunction "K_1") (pintype "bidirectional"))
      (node (ref "LED7") (pin "1") (pinfunction "K_1") (pintype "bidirectional"))
      (node (ref "LED8") (pin "1") (pinfunction "K_1") (pintype "bidirectional"))
      (node (ref "LED9") (pin "1") (pinfunction "K_1") (pintype "bidirectional"))
      (node (ref "OUTPUT") (pin "2") (pinfunction "2_2") (pintype "passive"))
      (node (ref "OUTPUT") (pin "4") (pinfunction "4_4") (pintype "passive"))
      (node (ref "OUTPUT") (pin "8") (pinfunction "8_8") (pintype "passive"))
      (node (ref "R1") (pin "S") (pinfunction "S_S") (pintype "passive"))
      (node (ref "R4") (pin "S") (pinfunction "S_S") (pintype "passive"))
      (node (ref "R5") (pin "S") (pinfunction "S_S") (pintype "passive"))
      (node (ref "SS") (pin "2") (pinfunction "S_2") (pintype "passive"))
      (node (ref "SW") (pin "8") (pinfunction "GND_8") (pintype "bidirectional"))
    )
    (net (code "102") (name "/SS") (class "Default")
      (node (ref "ADC") (pin "6") (pinfunction "~{CS}_6") (pintype "input"))
      (node (ref "R5") (pin "A") (pinfunction "A_A") (pintype "passive"))
      (node (ref "SS") (pin "1") (pinfunction "S_1") (pintype "passive"))
    )
    (net (code "103") (name "/V_DIV") (class "Default")
      (node (ref "ADC") (pin "1") (pinfunction "AIN1_1") (pintype "input"))
      (node (ref "ADC") (pin "2") (pinfunction "AIN2_2") (pintype "input"))
      (node (ref "AMUX_0") (pin "8") (pinfunction "D_8") (pintype "bidirectional"))
      (node (ref "R4") (pin "A") (pinfunction "A_A") (pintype "passive"))
    )
    (net (code "104") (name "Net-(R1-PadA)") (class "Default")
      (node (ref "R1") (pin "A") (pinfunction "A_A") (pintype "passive"))
      (node (ref "SV1") (pin "1") (pinfunction "1_1") (pintype "passive"))
    )
    (net (code "105") (name "Net-(R2-PadA)") (class "Default")
      (node (ref "R2") (pin "A") (pinfunction "A_A") (pintype "passive"))
      (node (ref "SV2") (pin "1") (pinfunction "1_1") (pintype "passive"))
    )
    (net (code "106") (name "unconnected-(R1-PadE)") (class "Default")
      (node (ref "R1") (pin "E") (pinfunction "E_E") (pintype "passive"))
    )
    (net (code "107") (name "unconnected-(R2-PadE)") (class "Default")
      (node (ref "R2") (pin "E") (pinfunction "E_E") (pintype "passive"))
    )
    (net (code "108") (name "unconnected-(R4-PadE)") (class "Default")
      (node (ref "R4") (pin "E") (pinfunction "E_E") (pintype "passive"))
    )
    (net (code "109") (name "unconnected-(R5-PadE)") (class "Default")
      (node (ref "R5") (pin "E") (pinfunction "E_E") (pintype "passive"))
    )
    (net (code "110") (name "unconnected-(SV1-Pad3)") (class "Default")
      (node (ref "SV1") (pin "3") (pinfunction "3_3") (pintype "passive"))
    )
    (net (code "111") (name "unconnected-(SV2-Pad3)") (class "Default")
      (node (ref "SV2") (pin "3") (pinfunction "3_3") (pintype "passive"))
    )
    (net (code "112") (name "unconnected-(SW-QK-Pad15)") (class "Default")
      (node (ref "SW") (pin "15") (pinfunction "QK_15") (pintype "bidirectional"))
    )
    (net (code "113") (name "unconnected-(SW-QL-Pad1)") (class "Default")
      (node (ref "SW") (pin "1") (pinfunction "QL_1") (pintype "bidirectional"))
    )
  )
)
